# PLD_Top.net
KiCad netlist of a schematic drawn in Altium Designer
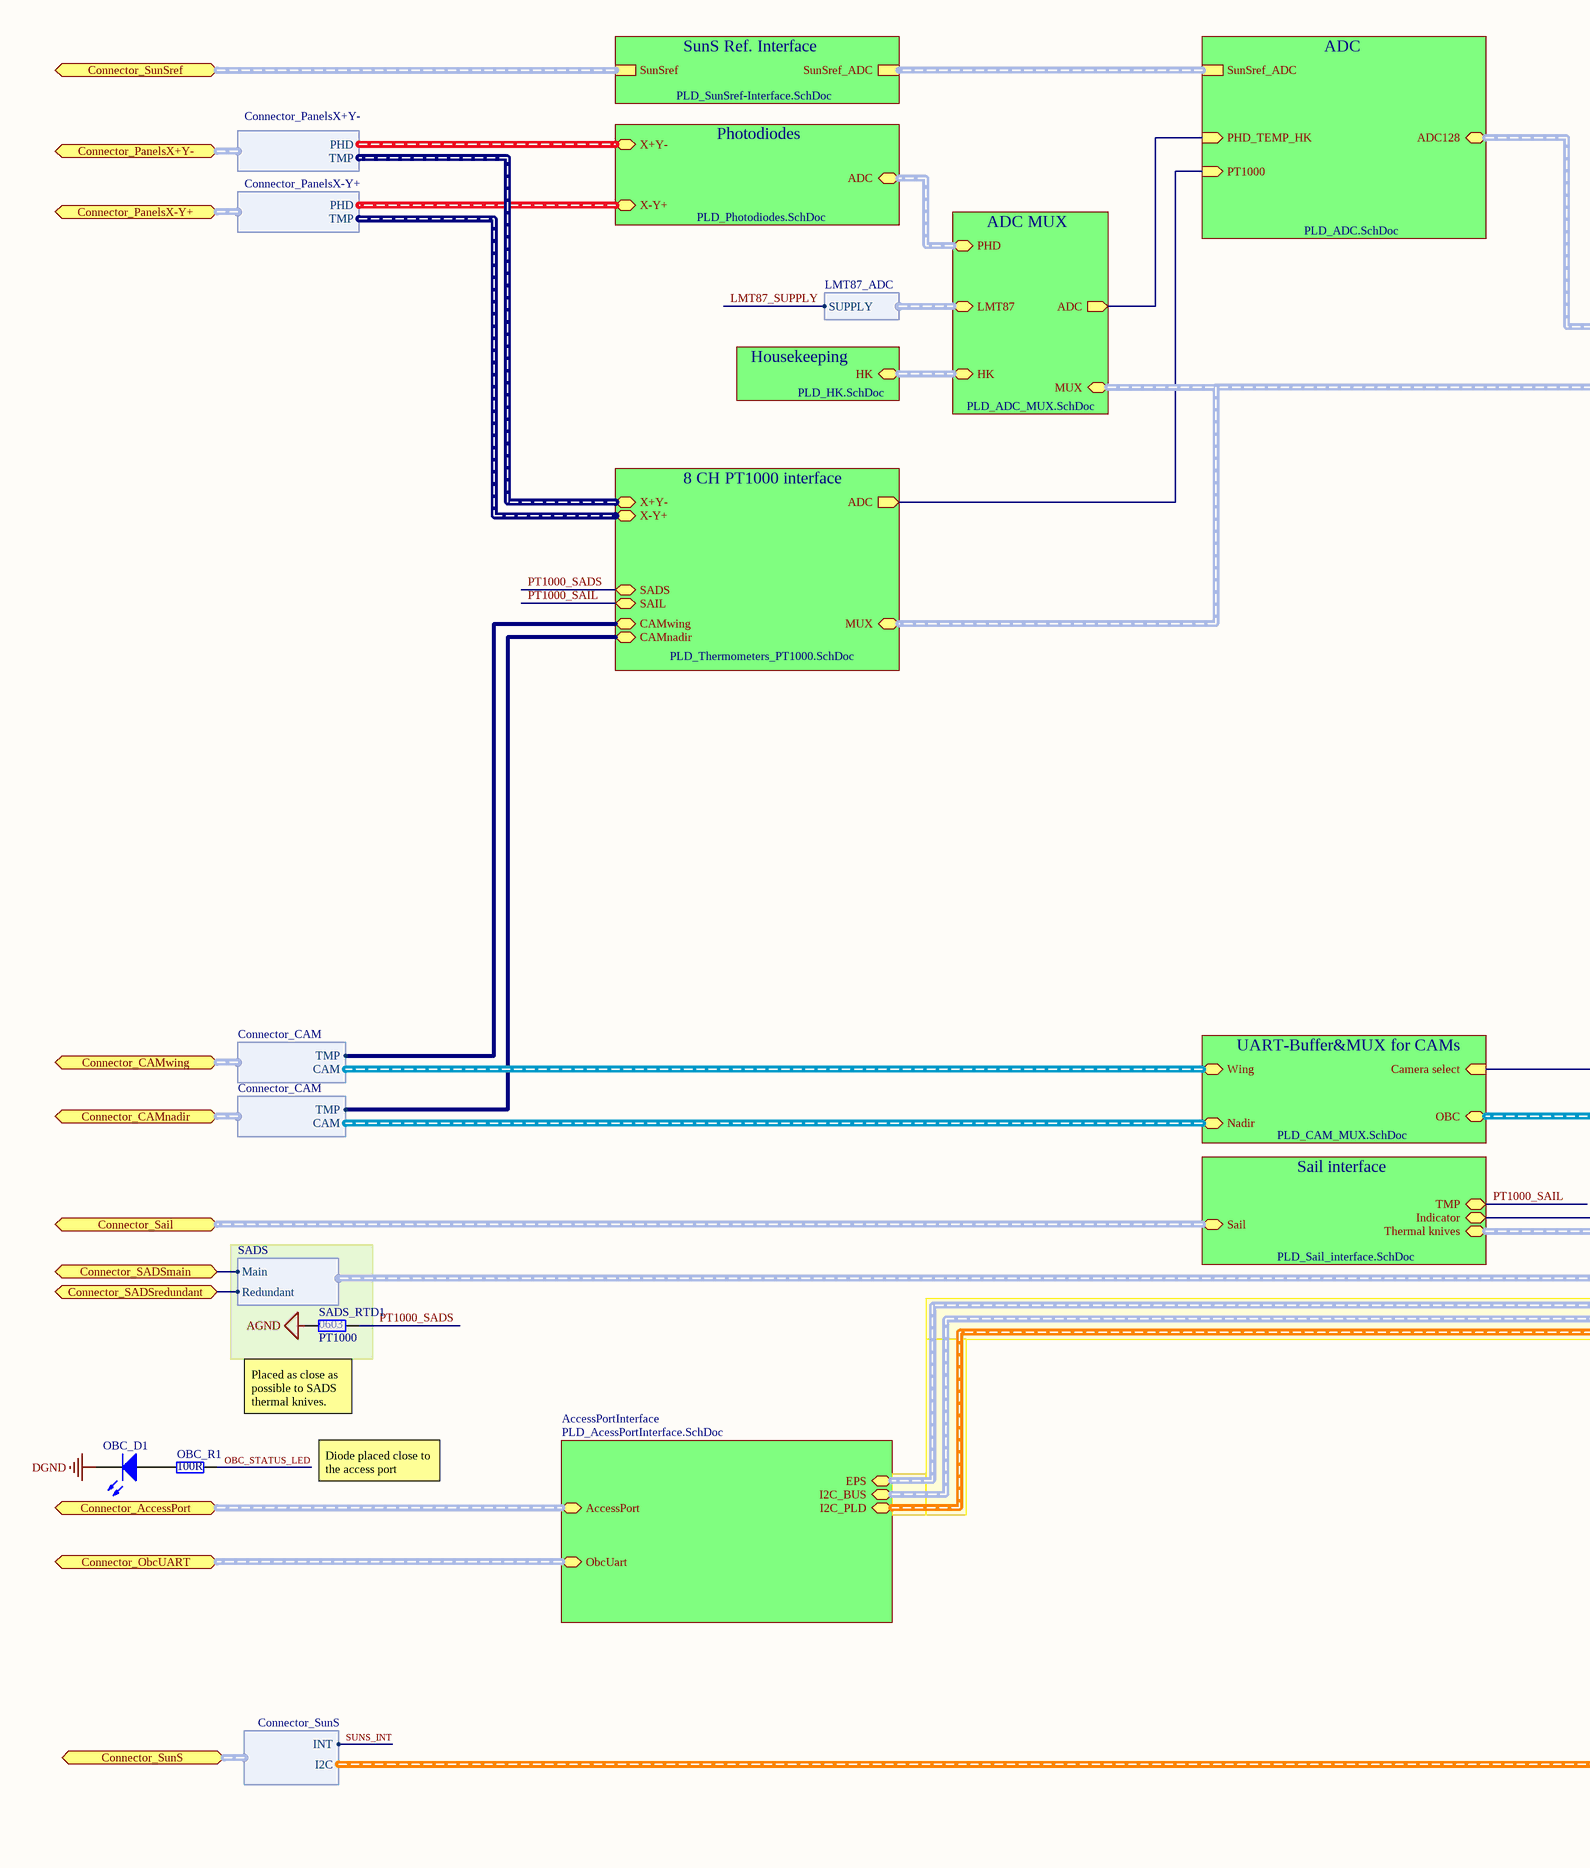
[diagram p0: PLD_Top.SchDoc, left]
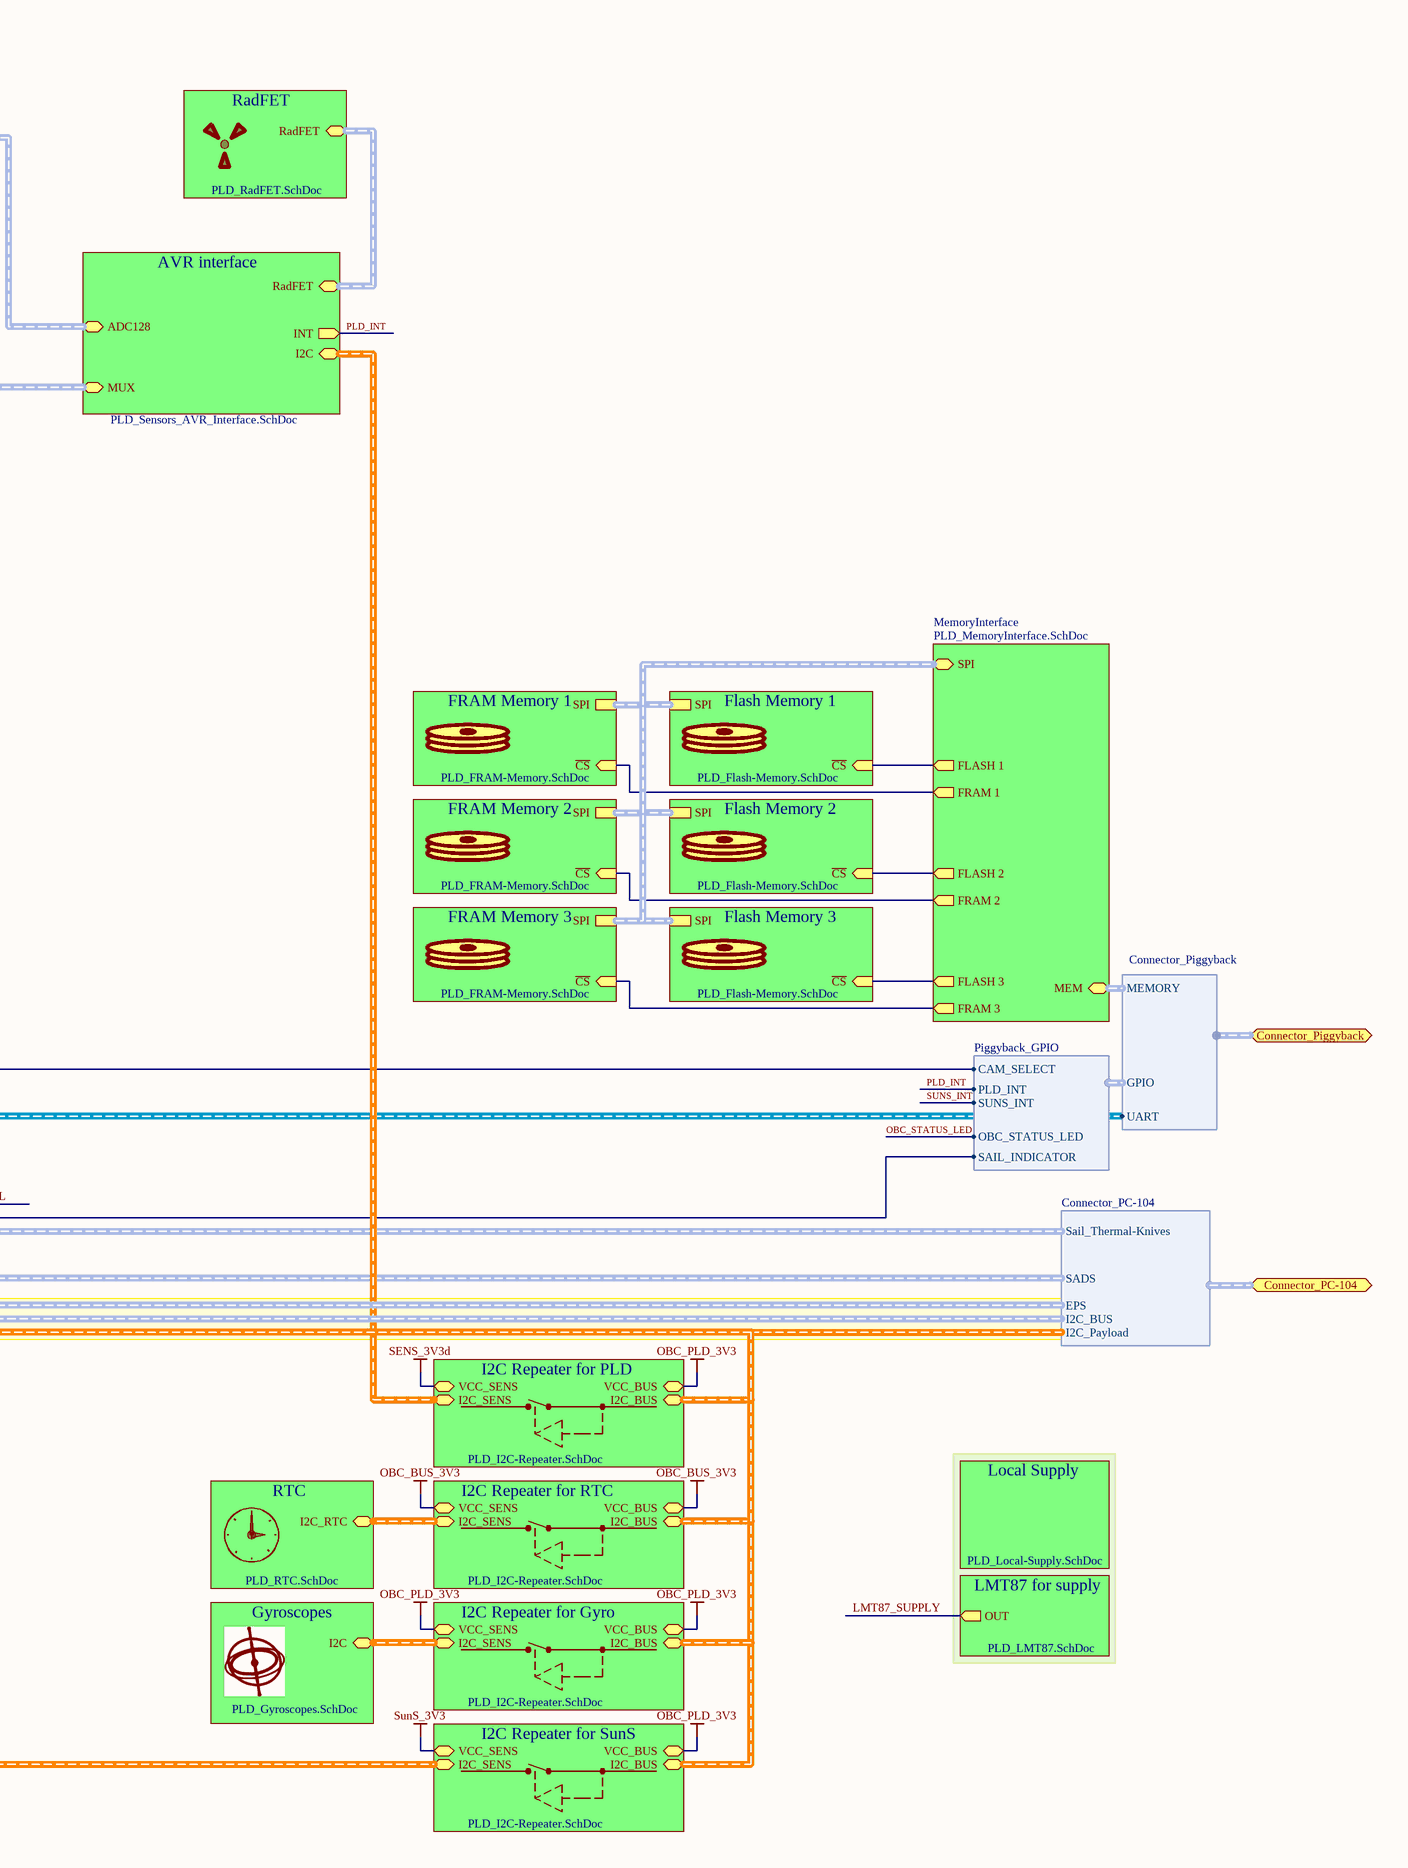
[diagram p1: PLD_Top.SchDoc, right]

(export (version "E")
  (design (tool "Eeschema 10.0.6"))
  (components
    (comp (ref "OBC_D1")
      (value "LEDX")
      (footprint "LED 0805 Blue")
      (description "Typical LED")
      (libsource (lib "diodes") (part "LEDX"))
    )
    (comp (ref "OBC_R1")
      (value "100R")
      (footprint "SMD_Resistor_0603")
      (libsource (lib "resistors") (part "Res"))
    )
    (comp (ref "SADS_RTD1")
      (value "PT1000")
      (footprint "SMD_Resistor_0603")
      (description "PT1000 Vishay PTS060301B100RP100")
      (fields
        (field (name "MANUFACTURER") "Vishay")
        (field (name "MANUFACTURERPARTNUMBER") "PTS060301B100RP100")
        (field (name "PACKAGE") "0603")
      )
      (libsource (lib "resistors") (part "PTS060301B100RP100"))
    )
  )
  (nets
    (net (code "54") (name "/OBC_STATUS_LED") (class "Default")
      (node (ref "OBC_R1") (pin "2") (pinfunction "2_2") (pintype "passive"))
    )
    (net (code "56") (name "/PT1000_SADS") (class "Default")
      (node (ref "SADS_RTD1") (pin "2") (pinfunction "2_2") (pintype "passive"))
    )
    (net (code "71") (name "AGND") (class "Default")
      (node (ref "SADS_RTD1") (pin "1") (pinfunction "1_1") (pintype "passive"))
    )
    (net (code "72") (name "DGND") (class "Default")
      (node (ref "OBC_D1") (pin "2") (pinfunction "K_2") (pintype "passive"))
    )
    (net (code "73") (name "Net-(OBC_D1-A)") (class "Default")
      (node (ref "OBC_D1") (pin "1") (pinfunction "A_1") (pintype "passive"))
      (node (ref "OBC_R1") (pin "1") (pinfunction "1_1") (pintype "passive"))
    )
  )
)
